# V4.net
KiCad netlist of a schematic drawn in Altium Designer
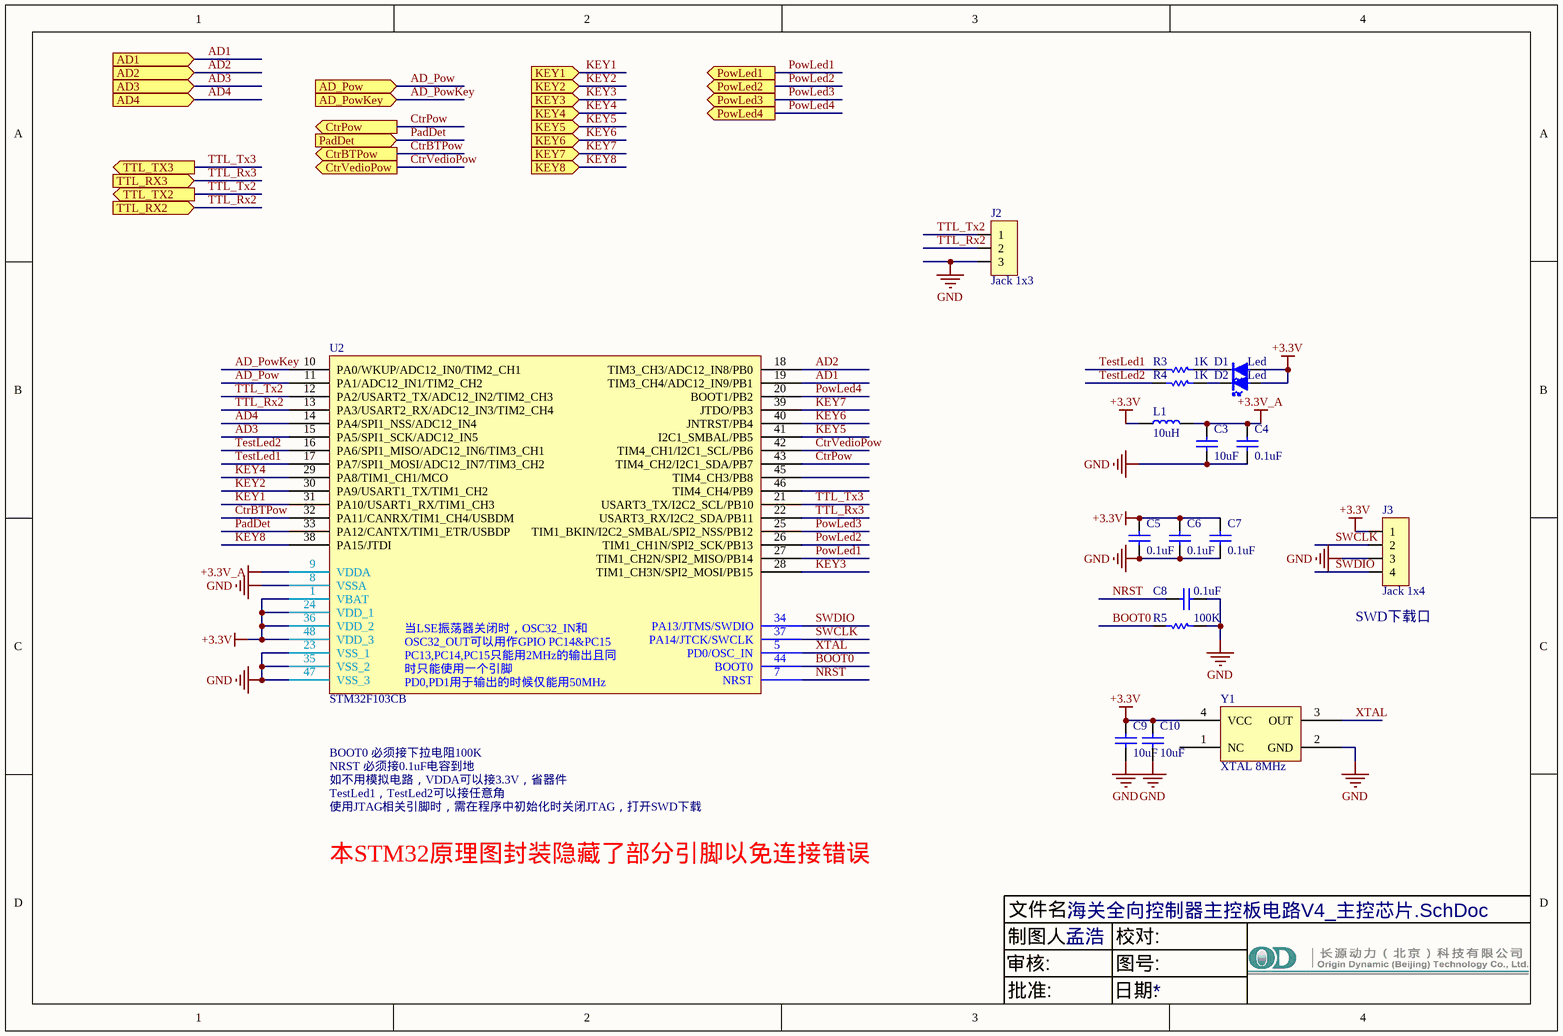
[diagram p0: 海关全向控制器主控板电路V4_主控芯片.SchDoc]

(export (version "E")
  (design (tool "Eeschema 10.0.6"))
  (components
    (comp (ref "C3")
      (value "10uF")
      (footprint "C0805")
      (description "CAP")
      (fields (field (name "PUBLISHER") "Altium Limited"))
      (libsource (lib "RLCYDF") (part "CAP"))
    )
    (comp (ref "C4")
      (value "0.1uF")
      (footprint "C0805")
      (description "CAP")
      (fields (field (name "PUBLISHER") "Altium Limited"))
      (libsource (lib "RLCYDF") (part "CAP"))
    )
    (comp (ref "C5")
      (value "0.1uF")
      (footprint "C0805")
      (description "CAP")
      (fields (field (name "PUBLISHER") "Altium Limited"))
      (libsource (lib "RLCYDF") (part "CAP"))
    )
    (comp (ref "C6")
      (value "0.1uF")
      (footprint "C0805")
      (description "CAP")
      (fields (field (name "PUBLISHER") "Altium Limited"))
      (libsource (lib "RLCYDF") (part "CAP"))
    )
    (comp (ref "C7")
      (value "0.1uF")
      (footprint "C0805")
      (description "CAP")
      (fields (field (name "PUBLISHER") "Altium Limited"))
      (libsource (lib "RLCYDF") (part "CAP"))
    )
    (comp (ref "C8")
      (value "0.1uF")
      (footprint "C0805")
      (description "CAP")
      (fields (field (name "PUBLISHER") "Altium Limited"))
      (libsource (lib "RLCYDF") (part "CAP"))
    )
    (comp (ref "C9")
      (value "10uF")
      (footprint "C0805")
      (description "CAP")
      (fields (field (name "PUBLISHER") "Altium Limited"))
      (libsource (lib "RLCYDF") (part "CAP"))
    )
    (comp (ref "C10")
      (value "10uF")
      (footprint "C0805")
      (description "CAP")
      (fields (field (name "PUBLISHER") "Altium Limited"))
      (libsource (lib "RLCYDF") (part "CAP"))
    )
    (comp (ref "D1")
      (value "Led")
      (footprint "LED0805")
      (description "light emitted diode")
      (libsource (lib "RLCYDF") (part "Led"))
    )
    (comp (ref "D2")
      (value "Led")
      (footprint "LED0805")
      (description "light emitted diode")
      (libsource (lib "RLCYDF") (part "Led"))
    )
    (comp (ref "J2")
      (value "Jack 1x3")
      (footprint "Jk1*3-2.0")
      (description "插座")
      (libsource (lib "Connector") (part "Jack 1x3"))
    )
    (comp (ref "J3")
      (value "Jack 1x4")
      (footprint "Jk1*4-2.0")
      (description "插座")
      (libsource (lib "Connector") (part "Jack 1x4"))
    )
    (comp (ref "L1") (value "10uH") (footprint "L0805") (libsource (lib "RLCYDF") (part "Inductor")))
    (comp (ref "R3") (value "1K") (footprint "R0805") (libsource (lib "RLCYDF") (part "Res")))
    (comp (ref "R4") (value "1K") (footprint "R0805") (libsource (lib "RLCYDF") (part "Res")))
    (comp (ref "R5") (value "100K") (footprint "R0805") (libsource (lib "RLCYDF") (part "Res")))
    (comp (ref "U2")
      (value "STM32F103CB")
      (footprint "LQFP48")
      (libsource (lib "stm32") (part "STM32F103Cx"))
    )
    (comp (ref "Y1") (value "XTAL 8MHz") (footprint "XTAL5032") (libsource (lib "Mic2805") (part "XTAL")))
  )
  (nets
    (net (code "1") (name "+3.3V") (class "Default")
      (node (ref "C10") (pin "1") (pinfunction "1_1") (pintype "passive"))
      (node (ref "C5") (pin "1") (pinfunction "1_1") (pintype "passive"))
      (node (ref "C6") (pin "1") (pinfunction "1_1") (pintype "passive"))
      (node (ref "C7") (pin "1") (pinfunction "1_1") (pintype "passive"))
      (node (ref "C9") (pin "1") (pinfunction "1_1") (pintype "passive"))
      (node (ref "D1") (pin "1") (pinfunction "A_1") (pintype "passive"))
      (node (ref "D2") (pin "1") (pinfunction "A_1") (pintype "passive"))
      (node (ref "J3") (pin "1") (pinfunction "1_1") (pintype "passive"))
      (node (ref "L1") (pin "1") (pinfunction "1_1") (pintype "passive"))
      (node (ref "U2") (pin "1") (pinfunction "VBAT_1") (pintype "power_in"))
      (node (ref "U2") (pin "24") (pinfunction "VDD_1_24") (pintype "power_in"))
      (node (ref "U2") (pin "36") (pinfunction "VDD_2_36") (pintype "power_in"))
      (node (ref "U2") (pin "48") (pinfunction "VDD_3_48") (pintype "power_in"))
      (node (ref "Y1") (pin "4") (pinfunction "VCC_4") (pintype "passive"))
    )
    (net (code "2") (name "+3.3V_A") (class "Default")
      (node (ref "C3") (pin "1") (pinfunction "1_1") (pintype "passive"))
      (node (ref "C4") (pin "1") (pinfunction "1_1") (pintype "passive"))
      (node (ref "L1") (pin "2") (pinfunction "2_2") (pintype "passive"))
      (node (ref "U2") (pin "9") (pinfunction "VDDA_9") (pintype "power_in"))
    )
    (net (code "3") (name "/AD1") (class "Default")
      (node (ref "U2") (pin "19") (pinfunction "TIM3_CH4/ADC12_IN9/PB1_19") (pintype "passive"))
    )
    (net (code "4") (name "/AD2") (class "Default")
      (node (ref "U2") (pin "18") (pinfunction "TIM3_CH3/ADC12_IN8/PB0_18") (pintype "passive"))
    )
    (net (code "5") (name "/AD3") (class "Default")
      (node (ref "U2") (pin "15") (pinfunction "PA5/SPI1_SCK/ADC12_IN5_15") (pintype "passive"))
    )
    (net (code "6") (name "/AD4") (class "Default")
      (node (ref "U2") (pin "14") (pinfunction "PA4/SPI1_NSS/ADC12_IN4_14") (pintype "passive"))
    )
    (net (code "7") (name "/AD_Pow") (class "Default")
      (node (ref "U2") (pin "11") (pinfunction "PA1/ADC12_IN1/TIM2_CH2_11") (pintype "passive"))
    )
    (net (code "8") (name "/AD_PowKey") (class "Default")
      (node (ref "U2") (pin "10") (pinfunction "PA0/WKUP/ADC12_IN0/TIM2_CH1_10") (pintype "passive"))
    )
    (net (code "9") (name "/BOOT0") (class "Default")
      (node (ref "R5") (pin "1") (pinfunction "1_1") (pintype "passive"))
      (node (ref "U2") (pin "44") (pinfunction "BOOT0_44") (pintype "passive"))
    )
    (net (code "10") (name "/CtrBTPow") (class "Default")
      (node (ref "U2") (pin "32") (pinfunction "PA11/CANRX/TIM1_CH4/USBDM_32") (pintype "passive"))
    )
    (net (code "11") (name "/CtrPow") (class "Default")
      (node (ref "U2") (pin "43") (pinfunction "TIM4_CH2/I2C1_SDA/PB7_43") (pintype "passive"))
    )
    (net (code "12") (name "/CtrVedioPow") (class "Default")
      (node (ref "U2") (pin "42") (pinfunction "TIM4_CH1/I2C1_SCL/PB6_42") (pintype "passive"))
    )
    (net (code "13") (name "/KEY1") (class "Default")
      (node (ref "U2") (pin "31") (pinfunction "PA10/USART1_RX/TIM1_CH3_31") (pintype "passive"))
    )
    (net (code "14") (name "/KEY2") (class "Default")
      (node (ref "U2") (pin "30") (pinfunction "PA9/USART1_TX/TIM1_CH2_30") (pintype "passive"))
    )
    (net (code "15") (name "/KEY3") (class "Default")
      (node (ref "U2") (pin "28") (pinfunction "TIM1_CH3N/SPI2_MOSI/PB15_28") (pintype "passive"))
    )
    (net (code "16") (name "/KEY4") (class "Default")
      (node (ref "U2") (pin "29") (pinfunction "PA8/TIM1_CH1/MCO_29") (pintype "passive"))
    )
    (net (code "17") (name "/KEY5") (class "Default")
      (node (ref "U2") (pin "41") (pinfunction "I2C1_SMBAL/PB5_41") (pintype "passive"))
    )
    (net (code "18") (name "/KEY6") (class "Default")
      (node (ref "U2") (pin "40") (pinfunction "JNTRST/PB4_40") (pintype "passive"))
    )
    (net (code "19") (name "/KEY7") (class "Default")
      (node (ref "U2") (pin "39") (pinfunction "JTDO/PB3_39") (pintype "passive"))
    )
    (net (code "20") (name "/KEY8") (class "Default")
      (node (ref "U2") (pin "38") (pinfunction "PA15/JTDI_38") (pintype "passive"))
    )
    (net (code "21") (name "/NRST") (class "Default")
      (node (ref "C8") (pin "1") (pinfunction "1_1") (pintype "passive"))
      (node (ref "U2") (pin "7") (pinfunction "NRST_7") (pintype "passive"))
    )
    (net (code "22") (name "/PadDet") (class "Default")
      (node (ref "U2") (pin "33") (pinfunction "PA12/CANTX/TIM1_ETR/USBDP_33") (pintype "passive"))
    )
    (net (code "23") (name "/PowLed1") (class "Default")
      (node (ref "U2") (pin "27") (pinfunction "TIM1_CH2N/SPI2_MISO/PB14_27") (pintype "passive"))
    )
    (net (code "24") (name "/PowLed2") (class "Default")
      (node (ref "U2") (pin "26") (pinfunction "TIM1_CH1N/SPI2_SCK/PB13_26") (pintype "passive"))
    )
    (net (code "25") (name "/PowLed3") (class "Default")
      (node (ref "U2") (pin "25") (pinfunction "TIM1_BKIN/I2C2_SMBAL/SPI2_NSS/PB12_25") (pintype "passive"))
    )
    (net (code "26") (name "/PowLed4") (class "Default")
      (node (ref "U2") (pin "20") (pinfunction "BOOT1/PB2_20") (pintype "passive"))
    )
    (net (code "27") (name "/SWCLK") (class "Default")
      (node (ref "J3") (pin "2") (pinfunction "2_2") (pintype "passive"))
      (node (ref "U2") (pin "37") (pinfunction "PA14/JTCK/SWCLK_37") (pintype "passive"))
    )
    (net (code "28") (name "/SWDIO") (class "Default")
      (node (ref "J3") (pin "4") (pinfunction "4_4") (pintype "passive"))
      (node (ref "U2") (pin "34") (pinfunction "PA13/JTMS/SWDIO_34") (pintype "passive"))
    )
    (net (code "29") (name "/TTL_Rx2") (class "Default")
      (node (ref "J2") (pin "2") (pinfunction "2_2") (pintype "passive"))
      (node (ref "U2") (pin "13") (pinfunction "PA3/USART2_RX/ADC12_IN3/TIM2_CH4_13") (pintype "passive"))
    )
    (net (code "30") (name "/TTL_Rx3") (class "Default")
      (node (ref "U2") (pin "22") (pinfunction "USART3_RX/I2C2_SDA/PB11_22") (pintype "passive"))
    )
    (net (code "31") (name "/TTL_Tx2") (class "Default")
      (node (ref "J2") (pin "1") (pinfunction "1_1") (pintype "passive"))
      (node (ref "U2") (pin "12") (pinfunction "PA2/USART2_TX/ADC12_IN2/TIM2_CH3_12") (pintype "passive"))
    )
    (net (code "32") (name "/TTL_Tx3") (class "Default")
      (node (ref "U2") (pin "21") (pinfunction "USART3_TX/I2C2_SCL/PB10_21") (pintype "passive"))
    )
    (net (code "33") (name "/TestLed1") (class "Default")
      (node (ref "R3") (pin "1") (pinfunction "1_1") (pintype "passive"))
      (node (ref "U2") (pin "17") (pinfunction "PA7/SPI1_MOSI/ADC12_IN7/TIM3_CH2_17") (pintype "passive"))
    )
    (net (code "34") (name "/TestLed2") (class "Default")
      (node (ref "R4") (pin "1") (pinfunction "1_1") (pintype "passive"))
      (node (ref "U2") (pin "16") (pinfunction "PA6/SPI1_MISO/ADC12_IN6/TIM3_CH1_16") (pintype "passive"))
    )
    (net (code "35") (name "/XTAL") (class "Default")
      (node (ref "U2") (pin "5") (pinfunction "PD0/OSC_IN_5") (pintype "passive"))
      (node (ref "Y1") (pin "3") (pinfunction "OUT_3") (pintype "passive"))
    )
    (net (code "36") (name "GND") (class "Default")
      (node (ref "C10") (pin "2") (pinfunction "2_2") (pintype "passive"))
      (node (ref "C3") (pin "2") (pinfunction "2_2") (pintype "passive"))
      (node (ref "C4") (pin "2") (pinfunction "2_2") (pintype "passive"))
      (node (ref "C5") (pin "2") (pinfunction "2_2") (pintype "passive"))
      (node (ref "C6") (pin "2") (pinfunction "2_2") (pintype "passive"))
      (node (ref "C7") (pin "2") (pinfunction "2_2") (pintype "passive"))
      (node (ref "C8") (pin "2") (pinfunction "2_2") (pintype "passive"))
      (node (ref "C9") (pin "2") (pinfunction "2_2") (pintype "passive"))
      (node (ref "J2") (pin "3") (pinfunction "3_3") (pintype "passive"))
      (node (ref "J3") (pin "3") (pinfunction "3_3") (pintype "passive"))
      (node (ref "R5") (pin "2") (pinfunction "2_2") (pintype "passive"))
      (node (ref "U2") (pin "23") (pinfunction "VSS_1_23") (pintype "power_in"))
      (node (ref "U2") (pin "35") (pinfunction "VSS_2_35") (pintype "power_in"))
      (node (ref "U2") (pin "47") (pinfunction "VSS_3_47") (pintype "power_in"))
      (node (ref "U2") (pin "8") (pinfunction "VSSA_8") (pintype "power_in"))
      (node (ref "Y1") (pin "2") (pinfunction "GND_2") (pintype "passive"))
    )
    (net (code "37") (name "Net-(D1-K)") (class "Default")
      (node (ref "D1") (pin "2") (pinfunction "K_2") (pintype "passive"))
      (node (ref "R3") (pin "2") (pinfunction "2_2") (pintype "passive"))
    )
    (net (code "38") (name "Net-(D2-K)") (class "Default")
      (node (ref "D2") (pin "2") (pinfunction "K_2") (pintype "passive"))
      (node (ref "R4") (pin "2") (pinfunction "2_2") (pintype "passive"))
    )
    (net (code "39") (name "unconnected-(U2-PC13-TAMPER-RTC-Pad2)") (class "Default")
      (node (ref "U2") (pin "2") (pinfunction "PC13-TAMPER-RTC_2") (pintype "passive"))
    )
    (net (code "40") (name "unconnected-(U2-PC14-OSC32_IN-Pad3)") (class "Default")
      (node (ref "U2") (pin "3") (pinfunction "PC14-OSC32_IN_3") (pintype "passive"))
    )
    (net (code "41") (name "unconnected-(U2-PC15-OSC32_OUT-Pad4)") (class "Default")
      (node (ref "U2") (pin "4") (pinfunction "PC15-OSC32_OUT_4") (pintype "passive"))
    )
    (net (code "42") (name "unconnected-(U2-PD1{slash}OSC_OUT-Pad6)") (class "Default")
      (node (ref "U2") (pin "6") (pinfunction "PD1/OSC_OUT_6") (pintype "passive"))
    )
    (net (code "43") (name "unconnected-(U2-TIM4_CH3{slash}PB8-Pad45)") (class "Default")
      (node (ref "U2") (pin "45") (pinfunction "TIM4_CH3/PB8_45") (pintype "passive"))
    )
    (net (code "44") (name "unconnected-(U2-TIM4_CH4{slash}PB9-Pad46)") (class "Default")
      (node (ref "U2") (pin "46") (pinfunction "TIM4_CH4/PB9_46") (pintype "passive"))
    )
    (net (code "45") (name "unconnected-(Y1-NC-Pad1)") (class "Default")
      (node (ref "Y1") (pin "1") (pinfunction "NC_1") (pintype "passive"))
    )
  )
)
